# 3V3.net
KiCad netlist of a schematic drawn in Altium Designer
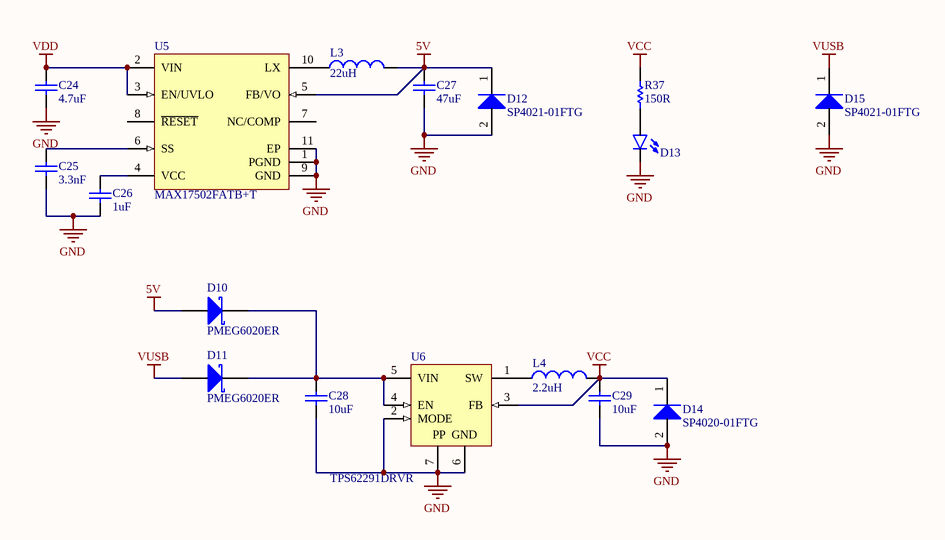
[diagram p0: 3V3.SchDoc]

(export (version "E")
  (design (tool "Eeschema 10.0.6"))
  (components
    (comp (ref "C24")
      (value "4.7uF")
      (footprint "C1210[3225X200]")
      (description "4.7uF 100V 10% 1210 (3225 Metric)")
      (fields (field (name "TOLERANCE") "10%") (field (name "PARTNUMBER") "GRJ32DC72A475KE11L"))
      (libsource (lib "Capacitors") (part "CAP_4.7uF_100V_1210_10%"))
    )
    (comp (ref "C25")
      (value "3.3nF")
      (footprint "C0402[1005X55]")
      (description "3.3nF 50V 10% 0402 (1005 Metric)")
      (fields (field (name "TOLERANCE") "10%") (field (name "PARTNUMBER") "GRM155R71H332KA01D"))
      (libsource (lib "Capacitors") (part "CAP_3.3nF_50V_0402_10%"))
    )
    (comp (ref "C26")
      (value "1uF")
      (footprint "C0402[1005X55]")
      (description "1uF 6.3V 10% 0402 (1005 Metric)")
      (fields (field (name "TOLERANCE") "10%") (field (name "PARTNUMBER") "GRM155R70J105KA12D"))
      (libsource (lib "Capacitors") (part "CAP_1uF_6.3V_0402_10%"))
    )
    (comp (ref "C27")
      (value "47uF")
      (footprint "C1210[3225X250]")
      (description "47uF 6.3V 10% 1210 (3225 Metric)")
      (fields (field (name "TOLERANCE") "10%") (field (name "PARTNUMBER") "GRM32ER70J476KE20L"))
      (libsource (lib "Capacitors") (part "CAP_47uF_6.3V_1210_10%"))
    )
    (comp (ref "C28")
      (value "10uF")
      (footprint "C0402[1005X55]")
      (description "10uF 6.3V 20% 0402 (1005 Metric)")
      (fields (field (name "TOLERANCE") "20%") (field (name "PARTNUMBER") "GRM155R60J106ME44D"))
      (libsource (lib "Capacitors") (part "CAP_10uF_6.3V_0402_20%"))
    )
    (comp (ref "C29")
      (value "10uF")
      (footprint "C0402[1005X55]")
      (description "10uF 6.3V 20% 0402 (1005 Metric)")
      (fields (field (name "TOLERANCE") "20%") (field (name "PARTNUMBER") "GRM155R60J106ME44D"))
      (libsource (lib "Capacitors") (part "CAP_10uF_6.3V_0402_20%"))
    )
    (comp (ref "D10")
      (value "PMEG6020ER")
      (footprint "SOD-123")
      (fields (field (name "PARTNUMBER") "PMEG6020ER,115") (field (name "MANUFACTURER") "NXP Semiconductors"))
      (libsource (lib "Diodes") (part "PMEG6020ER"))
    )
    (comp (ref "D11")
      (value "PMEG6020ER")
      (footprint "SOD-123")
      (fields (field (name "PARTNUMBER") "PMEG6020ER,115") (field (name "MANUFACTURER") "NXP Semiconductors"))
      (libsource (lib "Diodes") (part "PMEG6020ER"))
    )
    (comp (ref "D12")
      (value "SP4021-01FTG")
      (footprint "SOD-323")
      (fields (field (name "MANUFACTURER") "Littelfuse"))
      (libsource (lib "Diodes") (part "SP4021-01FTG"))
    )
    (comp (ref "D13")
      (value "LED_0603_GREEN_5mA")
      (footprint "LED0603")
      (fields (field (name "PARTNUMBER") "LTST-C193TGKT-5A") (field (name "MANUFACTURER") "Lite-On Inc."))
      (libsource (lib "LEDs") (part "LED_0603_GREEN_5mA"))
    )
    (comp (ref "D14")
      (value "SP4020-01FTG")
      (footprint "SOD323")
      (fields (field (name "MANUFACTURER") "Littelfuse"))
      (libsource (lib "Diodes") (part "SP4020-01FTG"))
    )
    (comp (ref "D15")
      (value "SP4021-01FTG")
      (footprint "SOD-323")
      (fields (field (name "MANUFACTURER") "Littelfuse"))
      (libsource (lib "Diodes-TVS") (part "SP4021-01FTG"))
    )
    (comp (ref "L3")
      (value "22uH")
      (footprint "SDR0604")
      (description "22uH 30% 1.1A 0604")
      (fields (field (name "PARTNUMBER") "SDR0604-220YL") (field (name "MANUFACTURER") "Bourns"))
      (libsource (lib "Inductors") (part "SDR0604-220YL"))
    )
    (comp (ref "L4")
      (value "2.2uH")
      (footprint "IND0805")
      (description "2.2uH 20% 1.7A 0805")
      (fields (field (name "PARTNUMBER") "LQM21PN2R2MGHL") (field (name "MANUFACTURER") "Murata"))
      (libsource (lib "Inductors") (part "IND_2.2uH_1.7A_0805_20%"))
    )
    (comp (ref "R37")
      (value "150R")
      (footprint "R0402[1005]")
      (description "150R 0.063W 1% 0402 (1005 Metric)")
      (fields (field (name "POWER") "0.063W") (field (name "TOLERANCE") "1%"))
      (libsource (lib "Resistors") (part "RES_150R_0402_1%"))
    )
    (comp (ref "U5")
      (value "MAX17502FATB+T")
      (footprint "TDFN-10-EP")
      (fields (field (name "MANUFACTURER") "Maxim Integrated"))
      (libsource (lib "ICs") (part "MAX17502FATB+T"))
    )
    (comp (ref "U6")
      (value "TPS62291DRVR")
      (footprint "WSON-6")
      (description "Voltage Regulators - Switching Regulators 2.25MHz 1A Step-Down Cnvrtr 3.3V Output")
      (fields (field (name "MANUFACTURER") "Texas Instruments"))
      (libsource (lib "ICs") (part "TPS62291DRVR"))
    )
  )
  (nets
    (net (code "1") (name "5V") (class "Default")
      (node (ref "C27") (pin "2") (pinfunction "2_2") (pintype "passive"))
      (node (ref "D10") (pin "2") (pinfunction "A_2") (pintype "passive"))
      (node (ref "D12") (pin "1") (pinfunction "K_1") (pintype "passive"))
      (node (ref "L3") (pin "2") (pinfunction "2_2") (pintype "passive"))
      (node (ref "U5") (pin "5") (pinfunction "FB/VO_5") (pintype "input"))
    )
    (net (code "2") (name "GND") (class "Default")
      (node (ref "C24") (pin "1") (pinfunction "1_1") (pintype "passive"))
      (node (ref "C25") (pin "1") (pinfunction "1_1") (pintype "passive"))
      (node (ref "C26") (pin "1") (pinfunction "1_1") (pintype "passive"))
      (node (ref "C27") (pin "1") (pinfunction "1_1") (pintype "passive"))
      (node (ref "C28") (pin "1") (pinfunction "1_1") (pintype "passive"))
      (node (ref "C29") (pin "1") (pinfunction "1_1") (pintype "passive"))
      (node (ref "D12") (pin "2") (pinfunction "A_2") (pintype "passive"))
      (node (ref "D13") (pin "C") (pinfunction "C_C") (pintype "passive"))
      (node (ref "D14") (pin "2") (pinfunction "A_2") (pintype "passive"))
      (node (ref "D15") (pin "2") (pinfunction "A_2") (pintype "passive"))
      (node (ref "U5") (pin "1") (pinfunction "PGND_1") (pintype "power_in"))
      (node (ref "U5") (pin "11") (pinfunction "EP_11") (pintype "power_in"))
      (node (ref "U5") (pin "9") (pinfunction "GND_9") (pintype "power_in"))
      (node (ref "U6") (pin "2") (pinfunction "MODE_2") (pintype "input"))
      (node (ref "U6") (pin "6") (pinfunction "GND_6") (pintype "power_in"))
      (node (ref "U6") (pin "7") (pinfunction "EP_7") (pintype "passive"))
    )
    (net (code "3") (name "Net-(D10-K)") (class "Default")
      (node (ref "C28") (pin "2") (pinfunction "2_2") (pintype "passive"))
      (node (ref "D10") (pin "1") (pinfunction "K_1") (pintype "passive"))
      (node (ref "D11") (pin "1") (pinfunction "K_1") (pintype "passive"))
      (node (ref "U6") (pin "4") (pinfunction "EN_4") (pintype "input"))
      (node (ref "U6") (pin "5") (pinfunction "VIN_5") (pintype "power_in"))
    )
    (net (code "4") (name "Net-(D13-PadA)") (class "Default")
      (node (ref "D13") (pin "A") (pinfunction "A_A") (pintype "passive"))
      (node (ref "R37") (pin "1") (pinfunction "1_1") (pintype "passive"))
    )
    (net (code "5") (name "Net-(U5-LX)") (class "Default")
      (node (ref "L3") (pin "1") (pinfunction "1_1") (pintype "passive"))
      (node (ref "U5") (pin "10") (pinfunction "LX_10") (pintype "passive"))
    )
    (net (code "6") (name "Net-(U5-SS)") (class "Default")
      (node (ref "C25") (pin "2") (pinfunction "2_2") (pintype "passive"))
      (node (ref "U5") (pin "6") (pinfunction "SS_6") (pintype "input"))
    )
    (net (code "7") (name "Net-(U5-VCC)") (class "Default")
      (node (ref "C26") (pin "2") (pinfunction "2_2") (pintype "passive"))
      (node (ref "U5") (pin "4") (pinfunction "VCC_4") (pintype "power_in"))
    )
    (net (code "8") (name "Net-(U6-SW)") (class "Default")
      (node (ref "L4") (pin "1") (pinfunction "1_1") (pintype "passive"))
      (node (ref "U6") (pin "1") (pinfunction "SW_1") (pintype "power_in"))
    )
    (net (code "9") (name "VCC") (class "Default")
      (node (ref "C29") (pin "2") (pinfunction "2_2") (pintype "passive"))
      (node (ref "D14") (pin "1") (pinfunction "K_1") (pintype "passive"))
      (node (ref "L4") (pin "2") (pinfunction "2_2") (pintype "passive"))
      (node (ref "R37") (pin "2") (pinfunction "2_2") (pintype "passive"))
      (node (ref "U6") (pin "3") (pinfunction "FB_3") (pintype "input"))
    )
    (net (code "10") (name "VDD") (class "Default")
      (node (ref "C24") (pin "2") (pinfunction "2_2") (pintype "passive"))
      (node (ref "U5") (pin "2") (pinfunction "VIN_2") (pintype "power_in"))
      (node (ref "U5") (pin "3") (pinfunction "EN/UVLO_3") (pintype "input"))
    )
    (net (code "11") (name "VUSB") (class "Default")
      (node (ref "D11") (pin "2") (pinfunction "A_2") (pintype "passive"))
      (node (ref "D15") (pin "1") (pinfunction "K_1") (pintype "passive"))
    )
    (net (code "12") (name "unconnected-(U5-NC{slash}COMP-Pad7)") (class "Default")
      (node (ref "U5") (pin "7") (pinfunction "NC/COMP_7") (pintype "passive"))
    )
    (net (code "13") (name "unconnected-(U5-~{RESET}-Pad8)") (class "Default")
      (node (ref "U5") (pin "8") (pinfunction "~{RESET}_8") (pintype "open_collector"))
    )
  )
)
